# WT108_main.net
KiCad netlist of a schematic drawn in Altium Designer
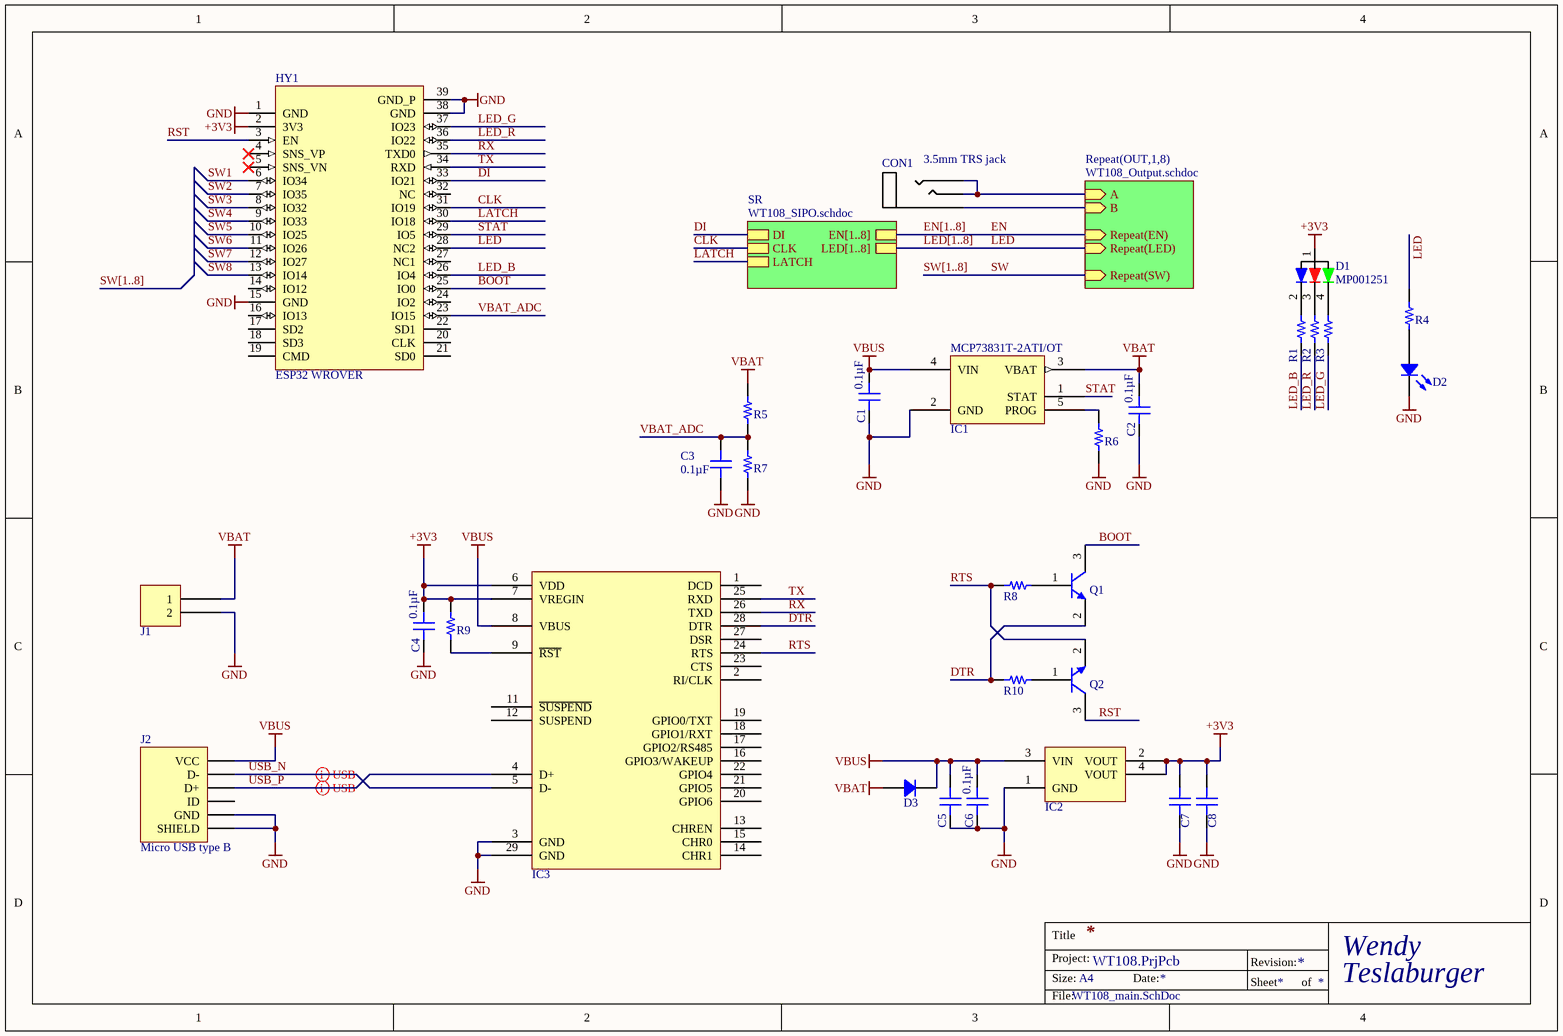
[diagram p0: WT108_main.SchDoc]

(export (version "E")
  (design (tool "Eeschema 10.0.6"))
  (components
    (comp (ref "C1")
      (value "0.1µF")
      (footprint "CAP 0603_1608")
      (description "CAP CER 0.1UF 50V X7R 0603")
      (fields (field (name "MANUFACTURER") "KEMET") (field (name "PART NUMBER") "C0603C104K5RAC7411"))
      (libsource (lib "Celestial Altium Library") (part "Capacitor"))
    )
    (comp (ref "C2")
      (value "0.1µF")
      (footprint "CAP 0603_1608")
      (description "CAP CER 0.1UF 50V X7R 0603")
      (fields (field (name "MANUFACTURER") "KEMET") (field (name "PART NUMBER") "C0603C104K5RAC7411"))
      (libsource (lib "Celestial Altium Library") (part "Capacitor"))
    )
    (comp (ref "C3")
      (value "0.1µF")
      (footprint "CAP 0603_1608")
      (description "CAP CER 0.1UF 50V X7R 0603")
      (fields (field (name "MANUFACTURER") "KEMET") (field (name "PART NUMBER") "C0603C104K5RAC7411"))
      (libsource (lib "Celestial Altium Library") (part "Capacitor"))
    )
    (comp (ref "C4")
      (value "0.1µF")
      (footprint "CAP 0603_1608")
      (description "CAP CER 0.1UF 50V X7R 0603")
      (fields (field (name "MANUFACTURER") "KEMET") (field (name "PART NUMBER") "C0603C104K5RAC7411"))
      (libsource (lib "Celestial Altium Library") (part "Capacitor"))
    )
    (comp (ref "C5")
      (value "10µF")
      (footprint "CAP 0805_2012")
      (description "CAP CER 10UF 6.3V X7R 0805")
      (fields
        (field (name "MANUFACTURER") "Murata Electronics")
        (field (name "PART NUMBER") "GCM21BR70J106KE22K")
      )
      (libsource (lib "Celestial Altium Library") (part "Capacitor"))
    )
    (comp (ref "C6")
      (value "0.1µF")
      (footprint "CAP 0603_1608")
      (description "CAP CER 0.1UF 50V X7R 0603")
      (fields (field (name "MANUFACTURER") "KEMET") (field (name "PART NUMBER") "C0603C104K5RAC7411"))
      (libsource (lib "Celestial Altium Library") (part "Capacitor"))
    )
    (comp (ref "C7")
      (value "10µF")
      (footprint "CAP 0805_2012")
      (description "CAP CER 10UF 6.3V X7R 0805")
      (fields
        (field (name "MANUFACTURER") "Murata Electronics")
        (field (name "PART NUMBER") "GCM21BR70J106KE22K")
      )
      (libsource (lib "Celestial Altium Library") (part "Capacitor"))
    )
    (comp (ref "C8")
      (value "10µF")
      (footprint "CAP 0805_2012")
      (description "CAP CER 10UF 6.3V X7R 0805")
      (fields
        (field (name "MANUFACTURER") "Murata Electronics")
        (field (name "PART NUMBER") "GCM21BR70J106KE22K")
      )
      (libsource (lib "Celestial Altium Library") (part "Capacitor"))
    )
    (comp (ref "CON1")
      (value "3.5mm TRS jack")
      (footprint "3.5mm socket, side mount")
      (libsource (lib "7c7_Connectors") (part "3.5mm TRS jack"))
    )
    (comp (ref "D1")
      (value "MP001251")
      (footprint "3528RGB")
      (description "LED, Red, Green, Blue, SMD, 3.5mm x 2.8mm, 120 °, Rectangular, R 20mA, G 20mA, B 20mA")
      (libsource (lib "7c7_discretes") (part "MP001251"))
    )
    (comp (ref "D2")
      (value "Green")
      (footprint "LED 0805_2012 GREEN")
      (description "LED GREEN 0805 SMD")
      (fields (field (name "MANUFACTURER") "Dialight") (field (name "PART NUMBER") "5990181007F"))
      (libsource (lib "Celestial Altium Library") (part "LED"))
    )
    (comp (ref "D3")
      (value "RB162MM-30TR")
      (footprint "SOD123F")
      (description "DIODE SCHOTTKY 30V 1A PMDU")
      (fields (field (name "MANUFACTURER") "Rohm Semiconductor"))
      (libsource (lib "Celestial Altium Library") (part "Diode"))
    )
    (comp (ref "HY1")
      (value "ESP32 WROVER")
      (footprint "ESP32 _WROVER")
      (libsource (lib "7c7_Modules") (part "ESP32_WROVER"))
    )
    (comp (ref "IC1")
      (value "MCP73831T-2ATI/OT")
      (footprint "MICROCHIP SOT-23-5 OT")
      (description "IC CONTROLLR LI-ION 4.2V SOT23-5")
      (fields (field (name "MANUFACTURER") "Microchip Technology"))
      (libsource (lib "Celestial Altium Library") (part "MICROCHIP MCP73831"))
    )
    (comp (ref "IC2")
      (value "LD1117AS33TR")
      (footprint "ST SOT-223")
      (description "IC REG LINEAR 3.3V 1A SOT223")
      (fields (field (name "MANUFACTURER") "STMicroelectronics"))
      (libsource (lib "Celestial Altium Library") (part "ST LD1117"))
    )
    (comp (ref "IC3")
      (value "CP2102N-A02-GQFN28R")
      (footprint "SILICON LABS QFN-28 5x5MM")
      (description "IC USB TO UART BRIDGE QFN28")
      (fields (field (name "MANUFACTURER") "Silicon Labs"))
      (libsource (lib "Celestial Altium Library") (part "Silicon Labs - CP2102N QFN28"))
    )
    (comp (ref "J1")
      (value "B2B-PH-K-S(LF)(SN)")
      (footprint "JST B2B-PH-K")
      (description "CONN HEADER VERT 2POS 2MM")
      (fields (field (name "MANUFACTURER") "JST Sales America Inc."))
      (libsource (lib "Celestial Altium Library") (part "2 Pin"))
    )
    (comp (ref "J2")
      (value "Micro USB type B")
      (footprint "10118194")
      (libsource (lib "7c7_Connectors") (part "MicroUSB_TypeB"))
    )
    (comp (ref "Q1")
      (value "BC849BLT1G")
      (footprint "ON SEMI SOT-23-3")
      (description "TRANS NPN 30V 0.1A SOT-23")
      (fields (field (name "MANUFACTURER") "ON Semiconductor"))
      (libsource (lib "Celestial Altium Library") (part "ON SEMI NPN SOT-23-3"))
    )
    (comp (ref "Q2")
      (value "BC849BLT1G")
      (footprint "ON SEMI SOT-23-3")
      (description "TRANS NPN 30V 0.1A SOT-23")
      (fields (field (name "MANUFACTURER") "ON Semiconductor"))
      (libsource (lib "Celestial Altium Library") (part "ON SEMI NPN SOT-23-3"))
    )
    (comp (ref "R1")
      (value "120 Ohms")
      (footprint "RES 0603_1608")
      (description "RES SMD 120 OHM 0.5% 1/10W 0603")
      (fields (field (name "MANUFACTURER") "Yageo") (field (name "PART NUMBER") "RT0603DRE07120RL"))
      (libsource (lib "Celestial Altium Library") (part "Resistor"))
    )
    (comp (ref "R2")
      (value "120 Ohms")
      (footprint "RES 0603_1608")
      (description "RES SMD 120 OHM 0.5% 1/10W 0603")
      (fields (field (name "MANUFACTURER") "Yageo") (field (name "PART NUMBER") "RT0603DRE07120RL"))
      (libsource (lib "Celestial Altium Library") (part "Resistor"))
    )
    (comp (ref "R3")
      (value "120 Ohms")
      (footprint "RES 0603_1608")
      (description "RES SMD 120 OHM 0.5% 1/10W 0603")
      (fields (field (name "MANUFACTURER") "Yageo") (field (name "PART NUMBER") "RT0603DRE07120RL"))
      (libsource (lib "Celestial Altium Library") (part "Resistor"))
    )
    (comp (ref "R4")
      (value "120 Ohms")
      (footprint "RES 0603_1608")
      (description "RES SMD 120 OHM 0.5% 1/10W 0603")
      (fields (field (name "MANUFACTURER") "Yageo") (field (name "PART NUMBER") "RT0603DRE07120RL"))
      (libsource (lib "Celestial Altium Library") (part "Resistor"))
    )
    (comp (ref "R5")
      (value "10 kOhms")
      (footprint "RES 0603_1608")
      (description "RES SMD 10K OHM 0.5% 1/10W 0603")
      (fields (field (name "MANUFACTURER") "Yageo") (field (name "PART NUMBER") "RT0603DRD0710KL"))
      (libsource (lib "Celestial Altium Library") (part "Resistor"))
    )
    (comp (ref "R6")
      (value "10 kOhms")
      (footprint "RES 0603_1608")
      (description "RES SMD 10K OHM 0.5% 1/10W 0603")
      (fields (field (name "MANUFACTURER") "Yageo") (field (name "PART NUMBER") "RT0603DRD0710KL"))
      (libsource (lib "Celestial Altium Library") (part "Resistor"))
    )
    (comp (ref "R7")
      (value "10 kOhms")
      (footprint "RES 0603_1608")
      (description "RES SMD 10K OHM 0.5% 1/10W 0603")
      (fields (field (name "MANUFACTURER") "Yageo") (field (name "PART NUMBER") "RT0603DRD0710KL"))
      (libsource (lib "Celestial Altium Library") (part "Resistor"))
    )
    (comp (ref "R8")
      (value "10 kOhms")
      (footprint "RES 0603_1608")
      (description "RES SMD 10K OHM 0.5% 1/10W 0603")
      (fields (field (name "MANUFACTURER") "Yageo") (field (name "PART NUMBER") "RT0603DRD0710KL"))
      (libsource (lib "Celestial Altium Library") (part "Resistor"))
    )
    (comp (ref "R9")
      (value "10 kOhms")
      (footprint "RES 0603_1608")
      (description "RES SMD 10K OHM 0.5% 1/10W 0603")
      (fields (field (name "MANUFACTURER") "Yageo") (field (name "PART NUMBER") "RT0603DRD0710KL"))
      (libsource (lib "Celestial Altium Library") (part "Resistor"))
    )
    (comp (ref "R10")
      (value "10 kOhms")
      (footprint "RES 0603_1608")
      (description "RES SMD 10K OHM 0.5% 1/10W 0603")
      (fields (field (name "MANUFACTURER") "Yageo") (field (name "PART NUMBER") "RT0603DRD0710KL"))
      (libsource (lib "Celestial Altium Library") (part "Resistor"))
    )
  )
  (nets
    (net (code "17") (name "+3V3") (class "Default")
      (node (ref "C4") (pin "2") (pinfunction "2_2") (pintype "passive"))
      (node (ref "C7") (pin "2") (pinfunction "2_2") (pintype "passive"))
      (node (ref "C8") (pin "2") (pinfunction "2_2") (pintype "passive"))
      (node (ref "D1") (pin "1") (pinfunction "COM_1") (pintype "power_in"))
      (node (ref "HY1") (pin "2") (pinfunction "3V3_2") (pintype "power_in"))
      (node (ref "IC2") (pin "2") (pinfunction "VOUT_2") (pintype "passive"))
      (node (ref "IC2") (pin "4") (pinfunction "VOUT_4") (pintype "passive"))
      (node (ref "IC3") (pin "6") (pinfunction "VDD_6") (pintype "passive"))
      (node (ref "IC3") (pin "7") (pinfunction "VREGIN_7") (pintype "passive"))
      (node (ref "R9") (pin "1") (pinfunction "1_1") (pintype "passive"))
    )
    (net (code "18") (name "/A") (class "Default")
      (node (ref "CON1") (pin "R") (pinfunction "R_R") (pintype "passive"))
      (node (ref "CON1") (pin "T") (pinfunction "T_T") (pintype "passive"))
    )
    (net (code "19") (name "/B") (class "Default")
      (node (ref "CON1") (pin "S") (pinfunction "S_S") (pintype "passive"))
    )
    (net (code "20") (name "/BOOT") (class "Default")
      (node (ref "HY1") (pin "25") (pinfunction "IO0_25") (pintype "bidirectional"))
      (node (ref "Q1") (pin "3") (pinfunction "C_3") (pintype "passive"))
    )
    (net (code "21") (name "/CLK") (class "Default")
      (node (ref "HY1") (pin "31") (pinfunction "IO19_31") (pintype "bidirectional"))
    )
    (net (code "22") (name "/DI") (class "Default")
      (node (ref "HY1") (pin "33") (pinfunction "IO21_33") (pintype "bidirectional"))
    )
    (net (code "23") (name "/DTR") (class "Default")
      (node (ref "IC3") (pin "28") (pinfunction "DTR_28") (pintype "passive"))
      (node (ref "Q1") (pin "2") (pinfunction "E_2") (pintype "passive"))
      (node (ref "R10") (pin "1") (pinfunction "1_1") (pintype "passive"))
    )
    (net (code "26") (name "/LATCH") (class "Default")
      (node (ref "HY1") (pin "30") (pinfunction "IO18_30") (pintype "bidirectional"))
    )
    (net (code "27") (name "/LED") (class "Default")
      (node (ref "HY1") (pin "28") (pinfunction "NC2_28") (pintype "bidirectional"))
      (node (ref "R4") (pin "1") (pinfunction "1_1") (pintype "passive"))
    )
    (net (code "29") (name "/LED_B") (class "Default")
      (node (ref "HY1") (pin "26") (pinfunction "IO4_26") (pintype "bidirectional"))
      (node (ref "R1") (pin "1") (pinfunction "1_1") (pintype "passive"))
    )
    (net (code "30") (name "/LED_G") (class "Default")
      (node (ref "HY1") (pin "37") (pinfunction "IO23_37") (pintype "bidirectional"))
      (node (ref "R3") (pin "1") (pinfunction "1_1") (pintype "passive"))
    )
    (net (code "31") (name "/LED_R") (class "Default")
      (node (ref "HY1") (pin "36") (pinfunction "IO22_36") (pintype "bidirectional"))
      (node (ref "R2") (pin "1") (pinfunction "1_1") (pintype "passive"))
    )
    (net (code "32") (name "/RST") (class "Default")
      (node (ref "HY1") (pin "3") (pinfunction "EN_3") (pintype "input"))
      (node (ref "Q2") (pin "3") (pinfunction "C_3") (pintype "passive"))
    )
    (net (code "33") (name "/RTS") (class "Default")
      (node (ref "IC3") (pin "24") (pinfunction "RTS_24") (pintype "passive"))
      (node (ref "Q2") (pin "2") (pinfunction "E_2") (pintype "passive"))
      (node (ref "R8") (pin "1") (pinfunction "1_1") (pintype "passive"))
    )
    (net (code "34") (name "/RX") (class "Default")
      (node (ref "HY1") (pin "35") (pinfunction "TXD0_35") (pintype "output"))
      (node (ref "IC3") (pin "26") (pinfunction "TXD_26") (pintype "passive"))
    )
    (net (code "35") (name "/STAT") (class "Default")
      (node (ref "HY1") (pin "29") (pinfunction "IO5_29") (pintype "bidirectional"))
      (node (ref "IC1") (pin "1") (pinfunction "STAT_1") (pintype "passive"))
    )
    (net (code "37") (name "/SW1") (class "Default")
      (node (ref "HY1") (pin "6") (pinfunction "IO34_6") (pintype "bidirectional"))
    )
    (net (code "38") (name "/SW2") (class "Default")
      (node (ref "HY1") (pin "7") (pinfunction "IO35_7") (pintype "bidirectional"))
    )
    (net (code "39") (name "/SW3") (class "Default")
      (node (ref "HY1") (pin "8") (pinfunction "IO32_8") (pintype "bidirectional"))
    )
    (net (code "40") (name "/SW4") (class "Default")
      (node (ref "HY1") (pin "9") (pinfunction "IO33_9") (pintype "bidirectional"))
    )
    (net (code "41") (name "/SW5") (class "Default")
      (node (ref "HY1") (pin "10") (pinfunction "IO25_10") (pintype "bidirectional"))
    )
    (net (code "42") (name "/SW6") (class "Default")
      (node (ref "HY1") (pin "11") (pinfunction "IO26_11") (pintype "bidirectional"))
    )
    (net (code "43") (name "/SW7") (class "Default")
      (node (ref "HY1") (pin "12") (pinfunction "IO27_12") (pintype "bidirectional"))
    )
    (net (code "44") (name "/SW8") (class "Default")
      (node (ref "HY1") (pin "13") (pinfunction "IO14_13") (pintype "bidirectional"))
    )
    (net (code "46") (name "/TX") (class "Default")
      (node (ref "HY1") (pin "34") (pinfunction "RXD_34") (pintype "input"))
      (node (ref "IC3") (pin "25") (pinfunction "RXD_25") (pintype "passive"))
    )
    (net (code "47") (name "/USB_N") (class "Default")
      (node (ref "IC3") (pin "5") (pinfunction "D-_5") (pintype "passive"))
      (node (ref "J2") (pin "2") (pinfunction "D-_2") (pintype "passive"))
    )
    (net (code "48") (name "/USB_P") (class "Default")
      (node (ref "IC3") (pin "4") (pinfunction "D+_4") (pintype "passive"))
      (node (ref "J2") (pin "3") (pinfunction "D+_3") (pintype "passive"))
    )
    (net (code "49") (name "/VBAT_ADC") (class "Default")
      (node (ref "C3") (pin "2") (pinfunction "2_2") (pintype "passive"))
      (node (ref "HY1") (pin "23") (pinfunction "IO15_23") (pintype "bidirectional"))
      (node (ref "R5") (pin "1") (pinfunction "1_1") (pintype "passive"))
      (node (ref "R7") (pin "2") (pinfunction "2_2") (pintype "passive"))
    )
    (net (code "50") (name "GND") (class "Default")
      (node (ref "C1") (pin "1") (pinfunction "1_1") (pintype "passive"))
      (node (ref "C2") (pin "1") (pinfunction "1_1") (pintype "passive"))
      (node (ref "C3") (pin "1") (pinfunction "1_1") (pintype "passive"))
      (node (ref "C4") (pin "1") (pinfunction "1_1") (pintype "passive"))
      (node (ref "C5") (pin "1") (pinfunction "1_1") (pintype "passive"))
      (node (ref "C6") (pin "1") (pinfunction "1_1") (pintype "passive"))
      (node (ref "C7") (pin "1") (pinfunction "1_1") (pintype "passive"))
      (node (ref "C8") (pin "1") (pinfunction "1_1") (pintype "passive"))
      (node (ref "D2") (pin "2") (pinfunction "2_2") (pintype "passive"))
      (node (ref "HY1") (pin "1") (pinfunction "GND_1") (pintype "power_in"))
      (node (ref "HY1") (pin "15") (pinfunction "GND_15") (pintype "power_in"))
      (node (ref "HY1") (pin "38") (pinfunction "GND_38") (pintype "power_in"))
      (node (ref "HY1") (pin "39") (pinfunction "GND_P_39") (pintype "power_in"))
      (node (ref "IC1") (pin "2") (pinfunction "GND_2") (pintype "passive"))
      (node (ref "IC2") (pin "1") (pinfunction "GND_1") (pintype "passive"))
      (node (ref "IC3") (pin "29") (pinfunction "GND_29") (pintype "passive"))
      (node (ref "IC3") (pin "3") (pinfunction "GND_3") (pintype "passive"))
      (node (ref "J1") (pin "2") (pinfunction "2_2") (pintype "passive"))
      (node (ref "J2") (pin "5") (pinfunction "GND_5") (pintype "passive"))
      (node (ref "J2") (pin "SH") (pinfunction "SHIELD_SH") (pintype "passive"))
      (node (ref "R6") (pin "1") (pinfunction "1_1") (pintype "passive"))
      (node (ref "R7") (pin "1") (pinfunction "1_1") (pintype "passive"))
    )
    (net (code "51") (name "Net-(D1-B)") (class "Default")
      (node (ref "D1") (pin "2") (pinfunction "B_2") (pintype "power_in"))
      (node (ref "R1") (pin "2") (pinfunction "2_2") (pintype "passive"))
    )
    (net (code "52") (name "Net-(D1-G)") (class "Default")
      (node (ref "D1") (pin "4") (pinfunction "G_4") (pintype "power_in"))
      (node (ref "R3") (pin "2") (pinfunction "2_2") (pintype "passive"))
    )
    (net (code "53") (name "Net-(D1-R)") (class "Default")
      (node (ref "D1") (pin "3") (pinfunction "R_3") (pintype "power_in"))
      (node (ref "R2") (pin "2") (pinfunction "2_2") (pintype "passive"))
    )
    (net (code "54") (name "Net-(D2-Pad1)") (class "Default")
      (node (ref "D2") (pin "1") (pinfunction "1_1") (pintype "passive"))
      (node (ref "R4") (pin "2") (pinfunction "2_2") (pintype "passive"))
    )
    (net (code "55") (name "Net-(IC1-PROG)") (class "Default")
      (node (ref "IC1") (pin "5") (pinfunction "PROG_5") (pintype "passive"))
      (node (ref "R6") (pin "2") (pinfunction "2_2") (pintype "passive"))
    )
    (net (code "56") (name "Net-(IC3-~{RST})") (class "Default")
      (node (ref "IC3") (pin "9") (pinfunction "~{RST}_9") (pintype "passive"))
      (node (ref "R9") (pin "2") (pinfunction "2_2") (pintype "passive"))
    )
    (net (code "57") (name "Net-(Q1-B)") (class "Default")
      (node (ref "Q1") (pin "1") (pinfunction "B_1") (pintype "passive"))
      (node (ref "R8") (pin "2") (pinfunction "2_2") (pintype "passive"))
    )
    (net (code "58") (name "Net-(Q2-B)") (class "Default")
      (node (ref "Q2") (pin "1") (pinfunction "B_1") (pintype "passive"))
      (node (ref "R10") (pin "2") (pinfunction "2_2") (pintype "passive"))
    )
    (net (code "59") (name "VBAT") (class "Default")
      (node (ref "C2") (pin "2") (pinfunction "2_2") (pintype "passive"))
      (node (ref "D3") (pin "1") (pinfunction "1_1") (pintype "passive"))
      (node (ref "IC1") (pin "3") (pinfunction "VBAT_3") (pintype "output"))
      (node (ref "J1") (pin "1") (pinfunction "1_1") (pintype "passive"))
      (node (ref "R5") (pin "2") (pinfunction "2_2") (pintype "passive"))
    )
    (net (code "60") (name "VBUS") (class "Default")
      (node (ref "C1") (pin "2") (pinfunction "2_2") (pintype "passive"))
      (node (ref "C5") (pin "2") (pinfunction "2_2") (pintype "passive"))
      (node (ref "C6") (pin "2") (pinfunction "2_2") (pintype "passive"))
      (node (ref "D3") (pin "2") (pinfunction "2_2") (pintype "passive"))
      (node (ref "IC1") (pin "4") (pinfunction "VIN_4") (pintype "passive"))
      (node (ref "IC2") (pin "3") (pinfunction "VIN_3") (pintype "passive"))
      (node (ref "IC3") (pin "8") (pinfunction "VBUS_8") (pintype "passive"))
      (node (ref "J2") (pin "1") (pinfunction "VCC_1") (pintype "passive"))
    )
    (net (code "61") (name "unconnected-(HY1-CLK-Pad20)") (class "Default")
      (node (ref "HY1") (pin "20") (pinfunction "CLK_20") (pintype "passive"))
    )
    (net (code "62") (name "unconnected-(HY1-CMD-Pad19)") (class "Default")
      (node (ref "HY1") (pin "19") (pinfunction "CMD_19") (pintype "passive"))
    )
    (net (code "63") (name "unconnected-(HY1-IO2-Pad24)") (class "Default")
      (node (ref "HY1") (pin "24") (pinfunction "IO2_24") (pintype "bidirectional"))
    )
    (net (code "64") (name "unconnected-(HY1-IO12-Pad14)") (class "Default")
      (node (ref "HY1") (pin "14") (pinfunction "IO12_14") (pintype "bidirectional"))
    )
    (net (code "65") (name "unconnected-(HY1-IO13-Pad16)") (class "Default")
      (node (ref "HY1") (pin "16") (pinfunction "IO13_16") (pintype "bidirectional"))
    )
    (net (code "66") (name "unconnected-(HY1-NC-Pad32)") (class "Default")
      (node (ref "HY1") (pin "32") (pinfunction "NC_32") (pintype "bidirectional"))
    )
    (net (code "67") (name "unconnected-(HY1-NC1-Pad27)") (class "Default")
      (node (ref "HY1") (pin "27") (pinfunction "NC1_27") (pintype "bidirectional"))
    )
    (net (code "68") (name "unconnected-(HY1-SD0-Pad21)") (class "Default")
      (node (ref "HY1") (pin "21") (pinfunction "SD0_21") (pintype "passive"))
    )
    (net (code "69") (name "unconnected-(HY1-SD1-Pad22)") (class "Default")
      (node (ref "HY1") (pin "22") (pinfunction "SD1_22") (pintype "passive"))
    )
    (net (code "70") (name "unconnected-(HY1-SD2-Pad17)") (class "Default")
      (node (ref "HY1") (pin "17") (pinfunction "SD2_17") (pintype "passive"))
    )
    (net (code "71") (name "unconnected-(HY1-SD3-Pad18)") (class "Default")
      (node (ref "HY1") (pin "18") (pinfunction "SD3_18") (pintype "passive"))
    )
    (net (code "72") (name "unconnected-(HY1-SNS_VN-Pad5)") (class "Default")
      (node (ref "HY1") (pin "5") (pinfunction "SNS_VN_5") (pintype "input+no_connect"))
    )
    (net (code "73") (name "unconnected-(HY1-SNS_VP-Pad4)") (class "Default")
      (node (ref "HY1") (pin "4") (pinfunction "SNS_VP_4") (pintype "input+no_connect"))
    )
    (net (code "74") (name "unconnected-(IC3-CHR0-Pad15)") (class "Default")
      (node (ref "IC3") (pin "15") (pinfunction "CHR0_15") (pintype "passive"))
    )
    (net (code "75") (name "unconnected-(IC3-CHR1-Pad14)") (class "Default")
      (node (ref "IC3") (pin "14") (pinfunction "CHR1_14") (pintype "passive"))
    )
    (net (code "76") (name "unconnected-(IC3-CHREN-Pad13)") (class "Default")
      (node (ref "IC3") (pin "13") (pinfunction "CHREN_13") (pintype "passive"))
    )
    (net (code "77") (name "unconnected-(IC3-CTS-Pad23)") (class "Default")
      (node (ref "IC3") (pin "23") (pinfunction "CTS_23") (pintype "passive"))
    )
    (net (code "78") (name "unconnected-(IC3-DCD-Pad1)") (class "Default")
      (node (ref "IC3") (pin "1") (pinfunction "DCD_1") (pintype "passive"))
    )
    (net (code "79") (name "unconnected-(IC3-DSR-Pad27)") (class "Default")
      (node (ref "IC3") (pin "27") (pinfunction "DSR_27") (pintype "passive"))
    )
    (net (code "80") (name "unconnected-(IC3-GPIO0{slash}TXT-Pad19)") (class "Default")
      (node (ref "IC3") (pin "19") (pinfunction "GPIO0/TXT_19") (pintype "passive"))
    )
    (net (code "81") (name "unconnected-(IC3-GPIO1{slash}RXT-Pad18)") (class "Default")
      (node (ref "IC3") (pin "18") (pinfunction "GPIO1/RXT_18") (pintype "passive"))
    )
    (net (code "82") (name "unconnected-(IC3-GPIO2{slash}RS485-Pad17)") (class "Default")
      (node (ref "IC3") (pin "17") (pinfunction "GPIO2/RS485_17") (pintype "passive"))
    )
    (net (code "83") (name "unconnected-(IC3-GPIO3{slash}WAKEUP-Pad16)") (class "Default")
      (node (ref "IC3") (pin "16") (pinfunction "GPIO3/WAKEUP_16") (pintype "passive"))
    )
    (net (code "84") (name "unconnected-(IC3-GPIO4-Pad22)") (class "Default")
      (node (ref "IC3") (pin "22") (pinfunction "GPIO4_22") (pintype "passive"))
    )
    (net (code "85") (name "unconnected-(IC3-GPIO5-Pad21)") (class "Default")
      (node (ref "IC3") (pin "21") (pinfunction "GPIO5_21") (pintype "passive"))
    )
    (net (code "86") (name "unconnected-(IC3-GPIO6-Pad20)") (class "Default")
      (node (ref "IC3") (pin "20") (pinfunction "GPIO6_20") (pintype "passive"))
    )
    (net (code "87") (name "unconnected-(IC3-RI{slash}CLK-Pad2)") (class "Default")
      (node (ref "IC3") (pin "2") (pinfunction "RI/CLK_2") (pintype "passive"))
    )
    (net (code "88") (name "unconnected-(IC3-SUSPEND-Pad12)") (class "Default")
      (node (ref "IC3") (pin "12") (pinfunction "SUSPEND_12") (pintype "passive"))
    )
    (net (code "89") (name "unconnected-(IC3-~{SUSPEND}-Pad11)") (class "Default")
      (node (ref "IC3") (pin "11") (pinfunction "~{SUSPEND}_11") (pintype "passive"))
    )
    (net (code "90") (name "unconnected-(J2-ID-Pad4)") (class "Default")
      (node (ref "J2") (pin "4") (pinfunction "ID_4") (pintype "passive"))
    )
  )
)
